# Modulo_de_expansao_01.net
KiCad netlist of a schematic drawn in EAGLE
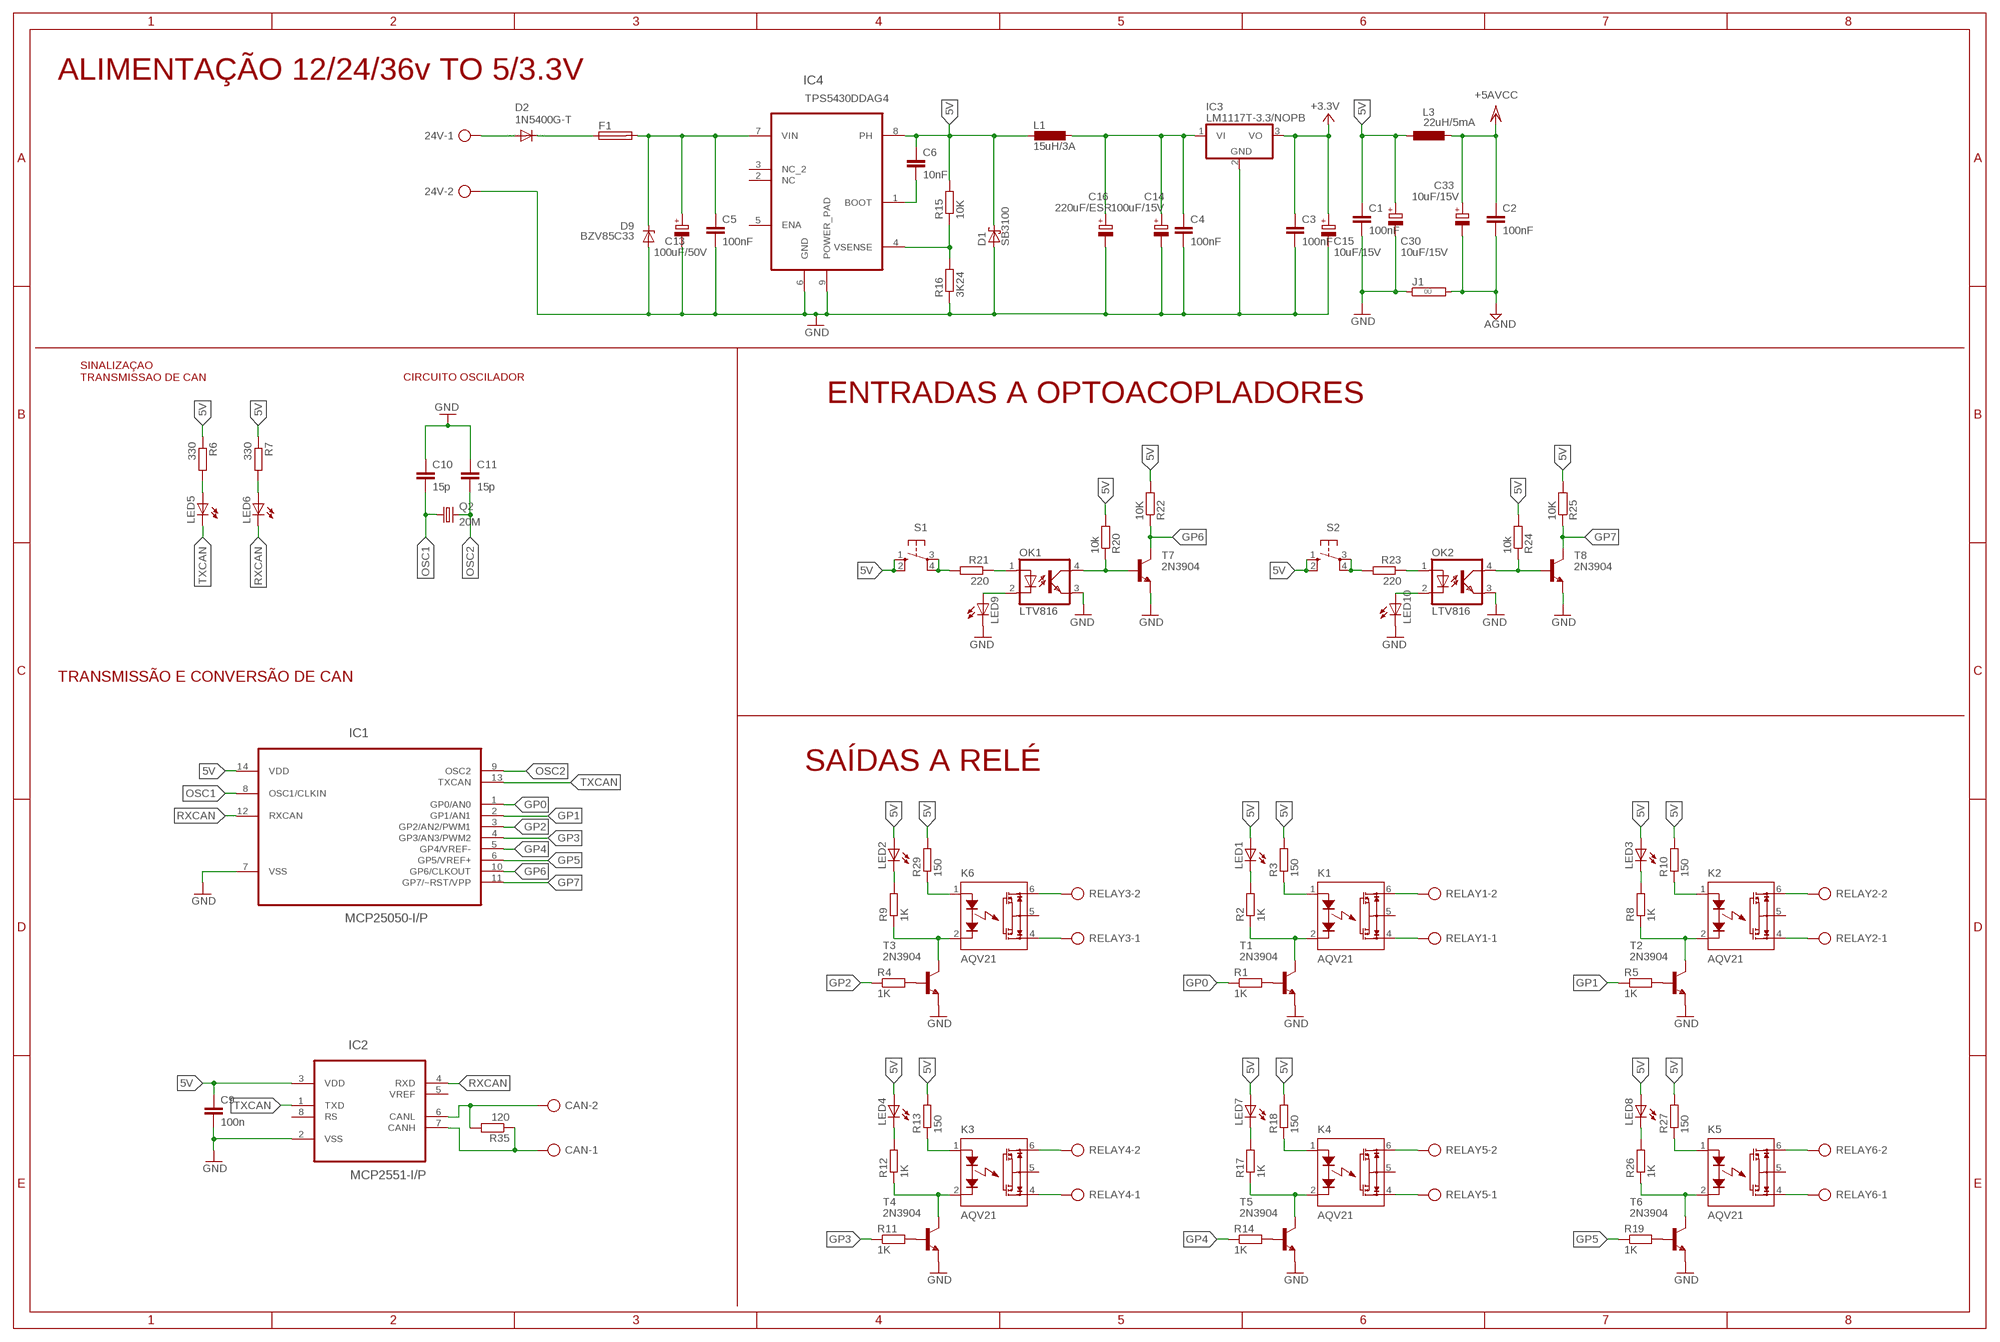
[diagram p0: schematic, sheet 1]

(export (version "E")
  (design (tool "Eeschema 10.0.6"))
  (components
    (comp (ref "24V")
      (value "AK300/2")
      (footprint "eagle-import:AK300_2")
      (libsource (lib "eagle-import") (part "AK300/2"))
    )
    (comp (ref "C1")
      (value "100nF")
      (footprint "eagle-import:C050-024X044")
      (libsource (lib "eagle-import") (part "C-EU050-024X044"))
    )
    (comp (ref "C2")
      (value "100nF")
      (footprint "eagle-import:C050-024X044")
      (libsource (lib "eagle-import") (part "C-EU050-024X044"))
    )
    (comp (ref "C3")
      (value "100nF")
      (footprint "eagle-import:C050-024X044")
      (libsource (lib "eagle-import") (part "C-EU050-024X044"))
    )
    (comp (ref "C4")
      (value "100nF")
      (footprint "eagle-import:C050-024X044")
      (libsource (lib "eagle-import") (part "C-EU050-024X044"))
    )
    (comp (ref "C5")
      (value "100nF")
      (footprint "eagle-import:C050-024X044")
      (libsource (lib "eagle-import") (part "C-EU050-024X044"))
    )
    (comp (ref "C6")
      (value "10nF")
      (footprint "eagle-import:C025-025X050")
      (libsource (lib "eagle-import") (part "C-EU025-025X050"))
    )
    (comp (ref "C9")
      (value "100n")
      (footprint "eagle-import:C050-024X044")
      (libsource (lib "eagle-import") (part "C-EU050-024X044"))
    )
    (comp (ref "C10")
      (value "15p")
      (footprint "eagle-import:C025-024X044")
      (libsource (lib "eagle-import") (part "C-EU025-024X044"))
    )
    (comp (ref "C11")
      (value "15p")
      (footprint "eagle-import:C025-024X044")
      (libsource (lib "eagle-import") (part "C-EU025-024X044"))
    )
    (comp (ref "C13")
      (value "100uF/50V")
      (footprint "eagle-import:E3,5-10")
      (libsource (lib "eagle-import") (part "CPOL-EUE3.5-10"))
    )
    (comp (ref "C14")
      (value "100uF/15V")
      (footprint "eagle-import:E2-5")
      (libsource (lib "eagle-import") (part "CPOL-EUE2-5"))
    )
    (comp (ref "C15")
      (value "10uF/15V")
      (footprint "eagle-import:E2-5")
      (libsource (lib "eagle-import") (part "CPOL-EUE2-5"))
    )
    (comp (ref "C16")
      (value "220uF/ESR")
      (footprint "eagle-import:E2,5-7")
      (libsource (lib "eagle-import") (part "CPOL-EUE2.5-7"))
    )
    (comp (ref "C30")
      (value "10uF/15V")
      (footprint "eagle-import:E2,5-6")
      (libsource (lib "eagle-import") (part "CPOL-EUE2.5-6"))
    )
    (comp (ref "C33")
      (value "10uF/15V")
      (footprint "eagle-import:E2,5-6")
      (libsource (lib "eagle-import") (part "CPOL-EUE2.5-6"))
    )
    (comp (ref "CAN")
      (value "AK300/2")
      (footprint "eagle-import:AK300_2")
      (libsource (lib "eagle-import") (part "AK300/2"))
    )
    (comp (ref "D1")
      (value "SB3100")
      (footprint "eagle-import:DO201T15")
      (libsource (lib "eagle-import") (part "SCHOTTKY-DIODEDO201T15"))
    )
    (comp (ref "D2")
      (value "1N5400G-T")
      (footprint "eagle-import:DO201-15")
      (libsource (lib "eagle-import") (part "1N5624"))
    )
    (comp (ref "D9")
      (value "BZV85C33")
      (footprint "eagle-import:DO34Z7")
      (libsource (lib "eagle-import") (part "BZV10"))
    )
    (comp (ref "F1")
      (value "TR5")
      (footprint "eagle-import:TR5")
      (libsource (lib "eagle-import") (part "TR5"))
    )
    (comp (ref "IC1")
      (value "MCP25050-I/P")
      (footprint "eagle-import:DIP254P762X432-14")
      (libsource (lib "eagle-import") (part "MCP25050-I/P"))
    )
    (comp (ref "IC2")
      (value "MCP2551-I/P")
      (footprint "eagle-import:DIP254P762X432-8")
      (libsource (lib "eagle-import") (part "MCP2551-I/P"))
    )
    (comp (ref "IC3")
      (value "LM1117T-3.3/NOPB")
      (footprint "eagle-import:TO220H")
      (libsource (lib "eagle-import") (part "LM340?-H12"))
    )
    (comp (ref "IC4")
      (value "TPS5430DDAG4")
      (footprint "eagle-import:SOIC127P600X170-9N")
      (fields (field (name "MPN") "TPS5430DDAG4"))
      (libsource (lib "eagle-import") (part "TPS5430DDAG4"))
    )
    (comp (ref "J1")
      (value "0R")
      (footprint "eagle-import:0R_10")
      (libsource (lib "eagle-import") (part "0R"))
    )
    (comp (ref "K1")
      (value "AQV21")
      (footprint "eagle-import:DIL06")
      (fields (field (name "MPN") "AQV210"))
      (libsource (lib "eagle-import") (part "AQV21"))
    )
    (comp (ref "K2")
      (value "AQV21")
      (footprint "eagle-import:DIL06")
      (fields (field (name "MPN") "AQV210"))
      (libsource (lib "eagle-import") (part "AQV21"))
    )
    (comp (ref "K3")
      (value "AQV21")
      (footprint "eagle-import:DIL06")
      (fields (field (name "MPN") "AQV210"))
      (libsource (lib "eagle-import") (part "AQV21"))
    )
    (comp (ref "K4")
      (value "AQV21")
      (footprint "eagle-import:DIL06")
      (fields (field (name "MPN") "AQV210"))
      (libsource (lib "eagle-import") (part "AQV21"))
    )
    (comp (ref "K5")
      (value "AQV21")
      (footprint "eagle-import:DIL06")
      (fields (field (name "MPN") "AQV210"))
      (libsource (lib "eagle-import") (part "AQV21"))
    )
    (comp (ref "K6")
      (value "AQV21")
      (footprint "eagle-import:DIL06")
      (fields (field (name "MPN") "AQV210"))
      (libsource (lib "eagle-import") (part "AQV21"))
    )
    (comp (ref "L1")
      (value "15uH/3A")
      (footprint "eagle-import:6000-XXXX-RC")
      (libsource (lib "eagle-import") (part "L-EU6000-XXX-RC"))
    )
    (comp (ref "L3")
      (value "22uH/5mA")
      (footprint "eagle-import:6000-XXXX-RC")
      (libsource (lib "eagle-import") (part "L-EU6000-XXX-RC"))
    )
    (comp (ref "LED1")
      (value "LED3MM")
      (footprint "eagle-import:LED3MM")
      (libsource (lib "eagle-import") (part "LED3MM"))
    )
    (comp (ref "LED2")
      (value "LED3MM")
      (footprint "eagle-import:LED3MM")
      (libsource (lib "eagle-import") (part "LED3MM"))
    )
    (comp (ref "LED3")
      (value "LED3MM")
      (footprint "eagle-import:LED3MM")
      (libsource (lib "eagle-import") (part "LED3MM"))
    )
    (comp (ref "LED4")
      (value "LED3MM")
      (footprint "eagle-import:LED3MM")
      (libsource (lib "eagle-import") (part "LED3MM"))
    )
    (comp (ref "LED5")
      (value "LED3MM")
      (footprint "eagle-import:LED3MM")
      (libsource (lib "eagle-import") (part "LED3MM"))
    )
    (comp (ref "LED6")
      (value "LED3MM")
      (footprint "eagle-import:LED3MM")
      (libsource (lib "eagle-import") (part "LED3MM"))
    )
    (comp (ref "LED7")
      (value "LED3MM")
      (footprint "eagle-import:LED3MM")
      (libsource (lib "eagle-import") (part "LED3MM"))
    )
    (comp (ref "LED8")
      (value "LED3MM")
      (footprint "eagle-import:LED3MM")
      (libsource (lib "eagle-import") (part "LED3MM"))
    )
    (comp (ref "LED9")
      (value "LED3MM")
      (footprint "eagle-import:LED3MM")
      (libsource (lib "eagle-import") (part "LED3MM"))
    )
    (comp (ref "LED10")
      (value "LED3MM")
      (footprint "eagle-import:LED3MM")
      (libsource (lib "eagle-import") (part "LED3MM"))
    )
    (comp (ref "OK1")
      (value "LTV816")
      (footprint "eagle-import:DIL04")
      (libsource (lib "eagle-import") (part "LTV816"))
    )
    (comp (ref "OK2")
      (value "LTV816")
      (footprint "eagle-import:DIL04")
      (libsource (lib "eagle-import") (part "LTV816"))
    )
    (comp (ref "Q2")
      (value "20M")
      (footprint "eagle-import:HC49_S")
      (libsource (lib "eagle-import") (part "CRYSTALHC49S"))
    )
    (comp (ref "R1")
      (value "1K")
      (footprint "eagle-import:0207_10")
      (libsource (lib "eagle-import") (part "R-EU_0207/10"))
    )
    (comp (ref "R2")
      (value "1K")
      (footprint "eagle-import:0207_10")
      (libsource (lib "eagle-import") (part "R-EU_0207/10"))
    )
    (comp (ref "R3")
      (value "150")
      (footprint "eagle-import:0207_10")
      (libsource (lib "eagle-import") (part "R-EU_0207/10"))
    )
    (comp (ref "R4")
      (value "1K")
      (footprint "eagle-import:0207_10")
      (libsource (lib "eagle-import") (part "R-EU_0207/10"))
    )
    (comp (ref "R5")
      (value "1K")
      (footprint "eagle-import:0207_10")
      (libsource (lib "eagle-import") (part "R-EU_0207/10"))
    )
    (comp (ref "R6")
      (value "330")
      (footprint "eagle-import:0207_10")
      (libsource (lib "eagle-import") (part "R-EU_0207/10"))
    )
    (comp (ref "R7")
      (value "330")
      (footprint "eagle-import:0207_10")
      (libsource (lib "eagle-import") (part "R-EU_0207/10"))
    )
    (comp (ref "R8")
      (value "1K")
      (footprint "eagle-import:0207_10")
      (libsource (lib "eagle-import") (part "R-EU_0207/10"))
    )
    (comp (ref "R9")
      (value "1K")
      (footprint "eagle-import:0207_10")
      (libsource (lib "eagle-import") (part "R-EU_0207/10"))
    )
    (comp (ref "R10")
      (value "150")
      (footprint "eagle-import:0207_10")
      (libsource (lib "eagle-import") (part "R-EU_0207/10"))
    )
    (comp (ref "R11")
      (value "1K")
      (footprint "eagle-import:0207_10")
      (libsource (lib "eagle-import") (part "R-EU_0207/10"))
    )
    (comp (ref "R12")
      (value "1K")
      (footprint "eagle-import:0207_10")
      (libsource (lib "eagle-import") (part "R-EU_0207/10"))
    )
    (comp (ref "R13")
      (value "150")
      (footprint "eagle-import:0207_10")
      (libsource (lib "eagle-import") (part "R-EU_0207/10"))
    )
    (comp (ref "R14")
      (value "1K")
      (footprint "eagle-import:0207_10")
      (libsource (lib "eagle-import") (part "R-EU_0207/10"))
    )
    (comp (ref "R15")
      (value "10K")
      (footprint "eagle-import:0207_10")
      (libsource (lib "eagle-import") (part "R-EU_0207/10"))
    )
    (comp (ref "R16")
      (value "3K24")
      (footprint "eagle-import:0207_10")
      (libsource (lib "eagle-import") (part "R-EU_0207/10"))
    )
    (comp (ref "R17")
      (value "1K")
      (footprint "eagle-import:0207_10")
      (libsource (lib "eagle-import") (part "R-EU_0207/10"))
    )
    (comp (ref "R18")
      (value "150")
      (footprint "eagle-import:0207_10")
      (libsource (lib "eagle-import") (part "R-EU_0207/10"))
    )
    (comp (ref "R19")
      (value "1K")
      (footprint "eagle-import:0207_10")
      (libsource (lib "eagle-import") (part "R-EU_0207/10"))
    )
    (comp (ref "R20")
      (value "10k")
      (footprint "eagle-import:0207_10")
      (libsource (lib "eagle-import") (part "R-EU_0207/10"))
    )
    (comp (ref "R21")
      (value "220")
      (footprint "eagle-import:0207_10")
      (libsource (lib "eagle-import") (part "R-EU_0207/10"))
    )
    (comp (ref "R22")
      (value "10K")
      (footprint "eagle-import:0207_10")
      (libsource (lib "eagle-import") (part "R-EU_0207/10"))
    )
    (comp (ref "R23")
      (value "220")
      (footprint "eagle-import:0207_10")
      (libsource (lib "eagle-import") (part "R-EU_0207/10"))
    )
    (comp (ref "R24")
      (value "10k")
      (footprint "eagle-import:0207_10")
      (libsource (lib "eagle-import") (part "R-EU_0207/10"))
    )
    (comp (ref "R25")
      (value "10K")
      (footprint "eagle-import:0207_10")
      (libsource (lib "eagle-import") (part "R-EU_0207/10"))
    )
    (comp (ref "R26")
      (value "1K")
      (footprint "eagle-import:0207_10")
      (libsource (lib "eagle-import") (part "R-EU_0207/10"))
    )
    (comp (ref "R27")
      (value "150")
      (footprint "eagle-import:0207_10")
      (libsource (lib "eagle-import") (part "R-EU_0207/10"))
    )
    (comp (ref "R29")
      (value "150")
      (footprint "eagle-import:0207_10")
      (libsource (lib "eagle-import") (part "R-EU_0207/10"))
    )
    (comp (ref "R35")
      (value "120")
      (footprint "eagle-import:0207_10")
      (libsource (lib "eagle-import") (part "R-EU_0207/10"))
    )
    (comp (ref "RELAY1")
      (value "AK300/2")
      (footprint "eagle-import:AK300_2")
      (libsource (lib "eagle-import") (part "AK300/2"))
    )
    (comp (ref "RELAY2")
      (value "AK300/2")
      (footprint "eagle-import:AK300_2")
      (libsource (lib "eagle-import") (part "AK300/2"))
    )
    (comp (ref "RELAY3")
      (value "AK300/2")
      (footprint "eagle-import:AK300_2")
      (libsource (lib "eagle-import") (part "AK300/2"))
    )
    (comp (ref "RELAY4")
      (value "AK300/2")
      (footprint "eagle-import:AK300_2")
      (libsource (lib "eagle-import") (part "AK300/2"))
    )
    (comp (ref "RELAY5")
      (value "AK300/2")
      (footprint "eagle-import:AK300_2")
      (libsource (lib "eagle-import") (part "AK300/2"))
    )
    (comp (ref "RELAY6")
      (value "AK300/2")
      (footprint "eagle-import:AK300_2")
      (libsource (lib "eagle-import") (part "AK300/2"))
    )
    (comp (ref "S1")
      (value "10-XX")
      (footprint "eagle-import:B3F-10XX")
      (fields (field (name "MPN") "B3F-1000"))
      (libsource (lib "eagle-import") (part "10-XX"))
    )
    (comp (ref "S2")
      (value "10-XX")
      (footprint "eagle-import:B3F-10XX")
      (fields (field (name "MPN") "B3F-1000"))
      (libsource (lib "eagle-import") (part "10-XX"))
    )
    (comp (ref "T1")
      (value "2N3904")
      (footprint "eagle-import:TO92")
      (libsource (lib "eagle-import") (part "2N3904"))
    )
    (comp (ref "T2")
      (value "2N3904")
      (footprint "eagle-import:TO92")
      (libsource (lib "eagle-import") (part "2N3904"))
    )
    (comp (ref "T3")
      (value "2N3904")
      (footprint "eagle-import:TO92")
      (libsource (lib "eagle-import") (part "2N3904"))
    )
    (comp (ref "T4")
      (value "2N3904")
      (footprint "eagle-import:TO92")
      (libsource (lib "eagle-import") (part "2N3904"))
    )
    (comp (ref "T5")
      (value "2N3904")
      (footprint "eagle-import:TO92")
      (libsource (lib "eagle-import") (part "2N3904"))
    )
    (comp (ref "T6")
      (value "2N3904")
      (footprint "eagle-import:TO92")
      (libsource (lib "eagle-import") (part "2N3904"))
    )
    (comp (ref "T7")
      (value "2N3904")
      (footprint "eagle-import:TO92")
      (libsource (lib "eagle-import") (part "2N3904"))
    )
    (comp (ref "T8")
      (value "2N3904")
      (footprint "eagle-import:TO92")
      (libsource (lib "eagle-import") (part "2N3904"))
    )
  )
  (nets
    (net (code "1") (name "+3.3V") (class "Default")
      (node (ref "C15") (pin "+") (pinfunction "+_+") (pintype "passive"))
      (node (ref "C3") (pin "1") (pinfunction "1_1") (pintype "passive"))
      (node (ref "IC3") (pin "3") (pinfunction "VO_3") (pintype "passive"))
    )
    (net (code "2") (name "+5AVCC") (class "Default")
      (node (ref "C2") (pin "1") (pinfunction "1_1") (pintype "passive"))
      (node (ref "C33") (pin "+") (pinfunction "+_+") (pintype "passive"))
      (node (ref "L3") (pin "2") (pinfunction "2_2") (pintype "passive"))
    )
    (net (code "3") (name "5V") (class "Default")
      (node (ref "C1") (pin "1") (pinfunction "1_1") (pintype "passive"))
      (node (ref "C30") (pin "+") (pinfunction "+_+") (pintype "passive"))
      (node (ref "C6") (pin "1") (pinfunction "1_1") (pintype "passive"))
      (node (ref "C9") (pin "1") (pinfunction "1_1") (pintype "passive"))
      (node (ref "D1") (pin "C") (pinfunction "C_C") (pintype "passive"))
      (node (ref "IC1") (pin "14") (pinfunction "VDD_14") (pintype "power_in"))
      (node (ref "IC2") (pin "3") (pinfunction "VDD_3") (pintype "power_in"))
      (node (ref "IC4") (pin "8") (pinfunction "PH_8") (pintype "input"))
      (node (ref "L1") (pin "2") (pinfunction "2_2") (pintype "passive"))
      (node (ref "L3") (pin "1") (pinfunction "1_1") (pintype "passive"))
      (node (ref "LED1") (pin "A") (pinfunction "A_A") (pintype "passive"))
      (node (ref "LED2") (pin "A") (pinfunction "A_A") (pintype "passive"))
      (node (ref "LED3") (pin "A") (pinfunction "A_A") (pintype "passive"))
      (node (ref "LED4") (pin "A") (pinfunction "A_A") (pintype "passive"))
      (node (ref "LED7") (pin "A") (pinfunction "A_A") (pintype "passive"))
      (node (ref "LED8") (pin "A") (pinfunction "A_A") (pintype "passive"))
      (node (ref "R10") (pin "2") (pinfunction "2_2") (pintype "passive"))
      (node (ref "R13") (pin "2") (pinfunction "2_2") (pintype "passive"))
      (node (ref "R15") (pin "2") (pinfunction "2_2") (pintype "passive"))
      (node (ref "R18") (pin "2") (pinfunction "2_2") (pintype "passive"))
      (node (ref "R20") (pin "2") (pinfunction "2_2") (pintype "passive"))
      (node (ref "R22") (pin "2") (pinfunction "2_2") (pintype "passive"))
      (node (ref "R24") (pin "2") (pinfunction "2_2") (pintype "passive"))
      (node (ref "R25") (pin "2") (pinfunction "2_2") (pintype "passive"))
      (node (ref "R27") (pin "2") (pinfunction "2_2") (pintype "passive"))
      (node (ref "R29") (pin "2") (pinfunction "2_2") (pintype "passive"))
      (node (ref "R3") (pin "2") (pinfunction "2_2") (pintype "passive"))
      (node (ref "R6") (pin "1") (pinfunction "1_1") (pintype "passive"))
      (node (ref "R7") (pin "1") (pinfunction "1_1") (pintype "passive"))
      (node (ref "S1") (pin "1") (pinfunction "S_1") (pintype "passive"))
      (node (ref "S1") (pin "2") (pinfunction "S1_2") (pintype "passive"))
      (node (ref "S2") (pin "1") (pinfunction "S_1") (pintype "passive"))
      (node (ref "S2") (pin "2") (pinfunction "S1_2") (pintype "passive"))
    )
    (net (code "4") (name "AGND") (class "Default")
      (node (ref "C2") (pin "2") (pinfunction "2_2") (pintype "passive"))
      (node (ref "C33") (pin "-") (pinfunction "-_-") (pintype "passive"))
      (node (ref "J1") (pin "2") (pinfunction "2_2") (pintype "passive"))
    )
    (net (code "5") (name "GND") (class "Default")
      (node (ref "24V") (pin "2") (pinfunction "KL_2") (pintype "passive"))
      (node (ref "C1") (pin "2") (pinfunction "2_2") (pintype "passive"))
      (node (ref "C10") (pin "1") (pinfunction "1_1") (pintype "passive"))
      (node (ref "C11") (pin "1") (pinfunction "1_1") (pintype "passive"))
      (node (ref "C13") (pin "-") (pinfunction "-_-") (pintype "passive"))
      (node (ref "C14") (pin "-") (pinfunction "-_-") (pintype "passive"))
      (node (ref "C15") (pin "-") (pinfunction "-_-") (pintype "passive"))
      (node (ref "C16") (pin "-") (pinfunction "-_-") (pintype "passive"))
      (node (ref "C3") (pin "2") (pinfunction "2_2") (pintype "passive"))
      (node (ref "C30") (pin "-") (pinfunction "-_-") (pintype "passive"))
      (node (ref "C4") (pin "2") (pinfunction "2_2") (pintype "passive"))
      (node (ref "C5") (pin "2") (pinfunction "2_2") (pintype "passive"))
      (node (ref "C9") (pin "2") (pinfunction "2_2") (pintype "passive"))
      (node (ref "D1") (pin "A") (pinfunction "A_A") (pintype "passive"))
      (node (ref "D9") (pin "A") (pinfunction "A_A") (pintype "passive"))
      (node (ref "IC1") (pin "7") (pinfunction "VSS_7") (pintype "passive"))
      (node (ref "IC2") (pin "2") (pinfunction "VSS_2") (pintype "power_in"))
      (node (ref "IC3") (pin "2") (pinfunction "GND_2") (pintype "passive"))
      (node (ref "IC4") (pin "6") (pinfunction "GND_6") (pintype "passive"))
      (node (ref "IC4") (pin "9") (pinfunction "POWER_PAD_9") (pintype "passive"))
      (node (ref "J1") (pin "1") (pinfunction "1_1") (pintype "passive"))
      (node (ref "LED10") (pin "K") (pinfunction "C_K") (pintype "passive"))
      (node (ref "LED9") (pin "K") (pinfunction "C_K") (pintype "passive"))
      (node (ref "OK1") (pin "3") (pinfunction "EMIT_3") (pintype "passive"))
      (node (ref "OK2") (pin "3") (pinfunction "EMIT_3") (pintype "passive"))
      (node (ref "R16") (pin "1") (pinfunction "1_1") (pintype "passive"))
      (node (ref "T1") (pin "3") (pinfunction "E_3") (pintype "passive"))
      (node (ref "T2") (pin "3") (pinfunction "E_3") (pintype "passive"))
      (node (ref "T3") (pin "3") (pinfunction "E_3") (pintype "passive"))
      (node (ref "T4") (pin "3") (pinfunction "E_3") (pintype "passive"))
      (node (ref "T5") (pin "3") (pinfunction "E_3") (pintype "passive"))
      (node (ref "T6") (pin "3") (pinfunction "E_3") (pintype "passive"))
      (node (ref "T7") (pin "3") (pinfunction "E_3") (pintype "passive"))
      (node (ref "T8") (pin "3") (pinfunction "E_3") (pintype "passive"))
    )
    (net (code "6") (name "GP0") (class "Default")
      (node (ref "IC1") (pin "1") (pinfunction "GP0/AN0_1") (pintype "bidirectional"))
      (node (ref "R1") (pin "1") (pinfunction "1_1") (pintype "passive"))
    )
    (net (code "7") (name "GP1") (class "Default")
      (node (ref "IC1") (pin "2") (pinfunction "GP1/AN1_2") (pintype "bidirectional"))
      (node (ref "R5") (pin "1") (pinfunction "1_1") (pintype "passive"))
    )
    (net (code "8") (name "GP2") (class "Default")
      (node (ref "IC1") (pin "3") (pinfunction "GP2/AN2/PWM1_3") (pintype "bidirectional"))
      (node (ref "R4") (pin "1") (pinfunction "1_1") (pintype "passive"))
    )
    (net (code "9") (name "GP3") (class "Default")
      (node (ref "IC1") (pin "4") (pinfunction "GP3/AN3/PWM2_4") (pintype "bidirectional"))
      (node (ref "R11") (pin "1") (pinfunction "1_1") (pintype "passive"))
    )
    (net (code "10") (name "GP4") (class "Default")
      (node (ref "IC1") (pin "5") (pinfunction "GP4/VREF-_5") (pintype "bidirectional"))
      (node (ref "R14") (pin "1") (pinfunction "1_1") (pintype "passive"))
    )
    (net (code "11") (name "GP5") (class "Default")
      (node (ref "IC1") (pin "6") (pinfunction "GP5/VREF+_6") (pintype "bidirectional"))
      (node (ref "R19") (pin "1") (pinfunction "1_1") (pintype "passive"))
    )
    (net (code "12") (name "GP6") (class "Default")
      (node (ref "IC1") (pin "10") (pinfunction "GP6/CLKOUT_10") (pintype "bidirectional"))
      (node (ref "R22") (pin "1") (pinfunction "1_1") (pintype "passive"))
      (node (ref "T7") (pin "1") (pinfunction "C_1") (pintype "passive"))
    )
    (net (code "13") (name "GP7") (class "Default")
      (node (ref "IC1") (pin "11") (pinfunction "GP7/~{RST/VPP}_11") (pintype "bidirectional"))
      (node (ref "R25") (pin "1") (pinfunction "1_1") (pintype "passive"))
      (node (ref "T8") (pin "1") (pinfunction "C_1") (pintype "passive"))
    )
    (net (code "14") (name "Net-(24VA-KL)") (class "Default")
      (node (ref "24V") (pin "1") (pinfunction "KL_1") (pintype "passive"))
      (node (ref "D2") (pin "A") (pinfunction "A_A") (pintype "passive"))
    )
    (net (code "15") (name "Net-(CANA-KL)") (class "Default")
      (node (ref "CAN") (pin "1") (pinfunction "KL_1") (pintype "passive"))
      (node (ref "IC2") (pin "7") (pinfunction "CANH_7") (pintype "bidirectional"))
      (node (ref "R35") (pin "1") (pinfunction "1_1") (pintype "passive"))
    )
    (net (code "16") (name "Net-(CANB-KL)") (class "Default")
      (node (ref "CAN") (pin "2") (pinfunction "KL_2") (pintype "passive"))
      (node (ref "IC2") (pin "6") (pinfunction "CANL_6") (pintype "bidirectional"))
      (node (ref "R35") (pin "2") (pinfunction "2_2") (pintype "passive"))
    )
    (net (code "17") (name "Net-(D2-PadC)") (class "Default")
      (node (ref "D2") (pin "C") (pinfunction "C_C") (pintype "passive"))
      (node (ref "F1") (pin "1") (pinfunction "1_1") (pintype "passive"))
    )
    (net (code "18") (name "Net-(IC3-VI)") (class "Default")
      (node (ref "C14") (pin "+") (pinfunction "+_+") (pintype "passive"))
      (node (ref "C16") (pin "+") (pinfunction "+_+") (pintype "passive"))
      (node (ref "C4") (pin "1") (pinfunction "1_1") (pintype "passive"))
      (node (ref "IC3") (pin "1") (pinfunction "VI_1") (pintype "input"))
      (node (ref "L1") (pin "1") (pinfunction "1_1") (pintype "passive"))
    )
    (net (code "19") (name "Net-(IC4-BOOT)") (class "Default")
      (node (ref "C6") (pin "2") (pinfunction "2_2") (pintype "passive"))
      (node (ref "IC4") (pin "1") (pinfunction "BOOT_1") (pintype "passive"))
    )
    (net (code "20") (name "Net-(IC4-VIN)") (class "Default")
      (node (ref "C13") (pin "+") (pinfunction "+_+") (pintype "passive"))
      (node (ref "C5") (pin "1") (pinfunction "1_1") (pintype "passive"))
      (node (ref "D9") (pin "C") (pinfunction "C_C") (pintype "passive"))
      (node (ref "F1") (pin "2") (pinfunction "2_2") (pintype "passive"))
      (node (ref "IC4") (pin "7") (pinfunction "VIN_7") (pintype "power_in"))
    )
    (net (code "21") (name "Net-(IC4-VSENSE)") (class "Default")
      (node (ref "IC4") (pin "4") (pinfunction "VSENSE_4") (pintype "output"))
      (node (ref "R15") (pin "1") (pinfunction "1_1") (pintype "passive"))
      (node (ref "R16") (pin "2") (pinfunction "2_2") (pintype "passive"))
    )
    (net (code "22") (name "Net-(K1-A)") (class "Default")
      (node (ref "K1") (pin "1") (pinfunction "A_1") (pintype "passive"))
      (node (ref "R3") (pin "1") (pinfunction "1_1") (pintype "passive"))
    )
    (net (code "23") (name "Net-(K1-D1)") (class "Default")
      (node (ref "K1") (pin "6") (pinfunction "D1_6") (pintype "passive"))
      (node (ref "RELAY1") (pin "2") (pinfunction "KL_2") (pintype "passive"))
    )
    (net (code "24") (name "Net-(K1-D2)") (class "Default")
      (node (ref "K1") (pin "4") (pinfunction "D2_4") (pintype "passive"))
      (node (ref "RELAY1") (pin "1") (pinfunction "KL_1") (pintype "passive"))
    )
    (net (code "25") (name "Net-(K1-K)") (class "Default")
      (node (ref "K1") (pin "2") (pinfunction "K_2") (pintype "passive"))
      (node (ref "R2") (pin "1") (pinfunction "1_1") (pintype "passive"))
      (node (ref "T1") (pin "1") (pinfunction "C_1") (pintype "passive"))
    )
    (net (code "26") (name "Net-(K2-A)") (class "Default")
      (node (ref "K2") (pin "1") (pinfunction "A_1") (pintype "passive"))
      (node (ref "R10") (pin "1") (pinfunction "1_1") (pintype "passive"))
    )
    (net (code "27") (name "Net-(K2-D1)") (class "Default")
      (node (ref "K2") (pin "6") (pinfunction "D1_6") (pintype "passive"))
      (node (ref "RELAY2") (pin "2") (pinfunction "KL_2") (pintype "passive"))
    )
    (net (code "28") (name "Net-(K2-D2)") (class "Default")
      (node (ref "K2") (pin "4") (pinfunction "D2_4") (pintype "passive"))
      (node (ref "RELAY2") (pin "1") (pinfunction "KL_1") (pintype "passive"))
    )
    (net (code "29") (name "Net-(K2-K)") (class "Default")
      (node (ref "K2") (pin "2") (pinfunction "K_2") (pintype "passive"))
      (node (ref "R8") (pin "1") (pinfunction "1_1") (pintype "passive"))
      (node (ref "T2") (pin "1") (pinfunction "C_1") (pintype "passive"))
    )
    (net (code "30") (name "Net-(K3-A)") (class "Default")
      (node (ref "K3") (pin "1") (pinfunction "A_1") (pintype "passive"))
      (node (ref "R13") (pin "1") (pinfunction "1_1") (pintype "passive"))
    )
    (net (code "31") (name "Net-(K3-D1)") (class "Default")
      (node (ref "K3") (pin "6") (pinfunction "D1_6") (pintype "passive"))
      (node (ref "RELAY4") (pin "2") (pinfunction "KL_2") (pintype "passive"))
    )
    (net (code "32") (name "Net-(K3-D2)") (class "Default")
      (node (ref "K3") (pin "4") (pinfunction "D2_4") (pintype "passive"))
      (node (ref "RELAY4") (pin "1") (pinfunction "KL_1") (pintype "passive"))
    )
    (net (code "33") (name "Net-(K3-K)") (class "Default")
      (node (ref "K3") (pin "2") (pinfunction "K_2") (pintype "passive"))
      (node (ref "R12") (pin "1") (pinfunction "1_1") (pintype "passive"))
      (node (ref "T4") (pin "1") (pinfunction "C_1") (pintype "passive"))
    )
    (net (code "34") (name "Net-(K4-A)") (class "Default")
      (node (ref "K4") (pin "1") (pinfunction "A_1") (pintype "passive"))
      (node (ref "R18") (pin "1") (pinfunction "1_1") (pintype "passive"))
    )
    (net (code "35") (name "Net-(K4-D1)") (class "Default")
      (node (ref "K4") (pin "6") (pinfunction "D1_6") (pintype "passive"))
      (node (ref "RELAY5") (pin "2") (pinfunction "KL_2") (pintype "passive"))
    )
    (net (code "36") (name "Net-(K4-D2)") (class "Default")
      (node (ref "K4") (pin "4") (pinfunction "D2_4") (pintype "passive"))
      (node (ref "RELAY5") (pin "1") (pinfunction "KL_1") (pintype "passive"))
    )
    (net (code "37") (name "Net-(K4-K)") (class "Default")
      (node (ref "K4") (pin "2") (pinfunction "K_2") (pintype "passive"))
      (node (ref "R17") (pin "1") (pinfunction "1_1") (pintype "passive"))
      (node (ref "T5") (pin "1") (pinfunction "C_1") (pintype "passive"))
    )
    (net (code "38") (name "Net-(K5-A)") (class "Default")
      (node (ref "K5") (pin "1") (pinfunction "A_1") (pintype "passive"))
      (node (ref "R27") (pin "1") (pinfunction "1_1") (pintype "passive"))
    )
    (net (code "39") (name "Net-(K5-D1)") (class "Default")
      (node (ref "K5") (pin "6") (pinfunction "D1_6") (pintype "passive"))
      (node (ref "RELAY6") (pin "2") (pinfunction "KL_2") (pintype "passive"))
    )
    (net (code "40") (name "Net-(K5-D2)") (class "Default")
      (node (ref "K5") (pin "4") (pinfunction "D2_4") (pintype "passive"))
      (node (ref "RELAY6") (pin "1") (pinfunction "KL_1") (pintype "passive"))
    )
    (net (code "41") (name "Net-(K5-K)") (class "Default")
      (node (ref "K5") (pin "2") (pinfunction "K_2") (pintype "passive"))
      (node (ref "R26") (pin "1") (pinfunction "1_1") (pintype "passive"))
      (node (ref "T6") (pin "1") (pinfunction "C_1") (pintype "passive"))
    )
    (net (code "42") (name "Net-(K6-A)") (class "Default")
      (node (ref "K6") (pin "1") (pinfunction "A_1") (pintype "passive"))
      (node (ref "R29") (pin "1") (pinfunction "1_1") (pintype "passive"))
    )
    (net (code "43") (name "Net-(K6-D1)") (class "Default")
      (node (ref "K6") (pin "6") (pinfunction "D1_6") (pintype "passive"))
      (node (ref "RELAY3") (pin "2") (pinfunction "KL_2") (pintype "passive"))
    )
    (net (code "44") (name "Net-(K6-D2)") (class "Default")
      (node (ref "K6") (pin "4") (pinfunction "D2_4") (pintype "passive"))
      (node (ref "RELAY3") (pin "1") (pinfunction "KL_1") (pintype "passive"))
    )
    (net (code "45") (name "Net-(K6-K)") (class "Default")
      (node (ref "K6") (pin "2") (pinfunction "K_2") (pintype "passive"))
      (node (ref "R9") (pin "1") (pinfunction "1_1") (pintype "passive"))
      (node (ref "T3") (pin "1") (pinfunction "C_1") (pintype "passive"))
    )
    (net (code "46") (name "Net-(LED1-C)") (class "Default")
      (node (ref "LED1") (pin "K") (pinfunction "C_K") (pintype "passive"))
      (node (ref "R2") (pin "2") (pinfunction "2_2") (pintype "passive"))
    )
    (net (code "47") (name "Net-(LED2-C)") (class "Default")
      (node (ref "LED2") (pin "K") (pinfunction "C_K") (pintype "passive"))
      (node (ref "R9") (pin "2") (pinfunction "2_2") (pintype "passive"))
    )
    (net (code "48") (name "Net-(LED3-C)") (class "Default")
      (node (ref "LED3") (pin "K") (pinfunction "C_K") (pintype "passive"))
      (node (ref "R8") (pin "2") (pinfunction "2_2") (pintype "passive"))
    )
    (net (code "49") (name "Net-(LED4-C)") (class "Default")
      (node (ref "LED4") (pin "K") (pinfunction "C_K") (pintype "passive"))
      (node (ref "R12") (pin "2") (pinfunction "2_2") (pintype "passive"))
    )
    (net (code "50") (name "Net-(LED5-PadA)") (class "Default")
      (node (ref "LED5") (pin "A") (pinfunction "A_A") (pintype "passive"))
      (node (ref "R6") (pin "2") (pinfunction "2_2") (pintype "passive"))
    )
    (net (code "51") (name "Net-(LED6-PadA)") (class "Default")
      (node (ref "LED6") (pin "A") (pinfunction "A_A") (pintype "passive"))
      (node (ref "R7") (pin "2") (pinfunction "2_2") (pintype "passive"))
    )
    (net (code "52") (name "Net-(LED7-C)") (class "Default")
      (node (ref "LED7") (pin "K") (pinfunction "C_K") (pintype "passive"))
      (node (ref "R17") (pin "2") (pinfunction "2_2") (pintype "passive"))
    )
    (net (code "53") (name "Net-(LED8-C)") (class "Default")
      (node (ref "LED8") (pin "K") (pinfunction "C_K") (pintype "passive"))
      (node (ref "R26") (pin "2") (pinfunction "2_2") (pintype "passive"))
    )
    (net (code "54") (name "Net-(OK1-A)") (class "Default")
      (node (ref "OK1") (pin "1") (pinfunction "A_1") (pintype "passive"))
      (node (ref "R21") (pin "1") (pinfunction "1_1") (pintype "passive"))
    )
    (net (code "55") (name "Net-(OK1-C)") (class "Default")
      (node (ref "LED9") (pin "A") (pinfunction "A_A") (pintype "passive"))
      (node (ref "OK1") (pin "2") (pinfunction "C_2") (pintype "passive"))
    )
    (net (code "56") (name "Net-(OK1-COL)") (class "Default")
      (node (ref "OK1") (pin "4") (pinfunction "COL_4") (pintype "passive"))
      (node (ref "R20") (pin "1") (pinfunction "1_1") (pintype "passive"))
      (node (ref "T7") (pin "2") (pinfunction "B_2") (pintype "passive"))
    )
    (net (code "57") (name "Net-(OK2-A)") (class "Default")
      (node (ref "OK2") (pin "1") (pinfunction "A_1") (pintype "passive"))
      (node (ref "R23") (pin "1") (pinfunction "1_1") (pintype "passive"))
    )
    (net (code "58") (name "Net-(OK2-C)") (class "Default")
      (node (ref "LED10") (pin "A") (pinfunction "A_A") (pintype "passive"))
      (node (ref "OK2") (pin "2") (pinfunction "C_2") (pintype "passive"))
    )
    (net (code "59") (name "Net-(OK2-COL)") (class "Default")
      (node (ref "OK2") (pin "4") (pinfunction "COL_4") (pintype "passive"))
      (node (ref "R24") (pin "1") (pinfunction "1_1") (pintype "passive"))
      (node (ref "T8") (pin "2") (pinfunction "B_2") (pintype "passive"))
    )
    (net (code "60") (name "Net-(S1-P)") (class "Default")
      (node (ref "R21") (pin "2") (pinfunction "2_2") (pintype "passive"))
      (node (ref "S1") (pin "3") (pinfunction "P_3") (pintype "passive"))
      (node (ref "S1") (pin "4") (pinfunction "P1_4") (pintype "passive"))
    )
    (net (code "61") (name "Net-(S2-P)") (class "Default")
      (node (ref "R23") (pin "2") (pinfunction "2_2") (pintype "passive"))
      (node (ref "S2") (pin "3") (pinfunction "P_3") (pintype "passive"))
      (node (ref "S2") (pin "4") (pinfunction "P1_4") (pintype "passive"))
    )
    (net (code "62") (name "Net-(T1-B)") (class "Default")
      (node (ref "R1") (pin "2") (pinfunction "2_2") (pintype "passive"))
      (node (ref "T1") (pin "2") (pinfunction "B_2") (pintype "passive"))
    )
    (net (code "63") (name "Net-(T2-B)") (class "Default")
      (node (ref "R5") (pin "2") (pinfunction "2_2") (pintype "passive"))
      (node (ref "T2") (pin "2") (pinfunction "B_2") (pintype "passive"))
    )
    (net (code "64") (name "Net-(T3-B)") (class "Default")
      (node (ref "R4") (pin "2") (pinfunction "2_2") (pintype "passive"))
      (node (ref "T3") (pin "2") (pinfunction "B_2") (pintype "passive"))
    )
    (net (code "65") (name "Net-(T4-B)") (class "Default")
      (node (ref "R11") (pin "2") (pinfunction "2_2") (pintype "passive"))
      (node (ref "T4") (pin "2") (pinfunction "B_2") (pintype "passive"))
    )
    (net (code "66") (name "Net-(T5-B)") (class "Default")
      (node (ref "R14") (pin "2") (pinfunction "2_2") (pintype "passive"))
      (node (ref "T5") (pin "2") (pinfunction "B_2") (pintype "passive"))
    )
    (net (code "67") (name "Net-(T6-B)") (class "Default")
      (node (ref "R19") (pin "2") (pinfunction "2_2") (pintype "passive"))
      (node (ref "T6") (pin "2") (pinfunction "B_2") (pintype "passive"))
    )
    (net (code "68") (name "OSC1") (class "Default")
      (node (ref "C10") (pin "2") (pinfunction "2_2") (pintype "passive"))
      (node (ref "IC1") (pin "8") (pinfunction "OSC1/CLKIN_8") (pintype "input"))
      (node (ref "Q2") (pin "1") (pinfunction "1_1") (pintype "passive"))
    )
    (net (code "69") (name "OSC2") (class "Default")
      (node (ref "C11") (pin "2") (pinfunction "2_2") (pintype "passive"))
      (node (ref "IC1") (pin "9") (pinfunction "OSC2_9") (pintype "output"))
      (node (ref "Q2") (pin "2") (pinfunction "2_2") (pintype "passive"))
    )
    (net (code "70") (name "RXCAN") (class "Default")
      (node (ref "IC1") (pin "12") (pinfunction "RXCAN_12") (pintype "input"))
      (node (ref "IC2") (pin "4") (pinfunction "RXD_4") (pintype "output"))
      (node (ref "LED6") (pin "K") (pinfunction "C_K") (pintype "passive"))
    )
    (net (code "71") (name "TXCAN") (class "Default")
      (node (ref "IC1") (pin "13") (pinfunction "TXCAN_13") (pintype "output"))
      (node (ref "IC2") (pin "1") (pinfunction "TXD_1") (pintype "input"))
      (node (ref "LED5") (pin "K") (pinfunction "C_K") (pintype "passive"))
    )
    (net (code "72") (name "unconnected-(IC2-RS-Pad8)") (class "Default")
      (node (ref "IC2") (pin "8") (pinfunction "RS_8") (pintype "input"))
    )
    (net (code "73") (name "unconnected-(IC2-VREF-Pad5)") (class "Default")
      (node (ref "IC2") (pin "5") (pinfunction "VREF_5") (pintype "output"))
    )
    (net (code "74") (name "unconnected-(IC4-ENA-Pad5)") (class "Default")
      (node (ref "IC4") (pin "5") (pinfunction "ENA_5") (pintype "input"))
    )
    (net (code "75") (name "unconnected-(IC4-NC-Pad2)") (class "Default")
      (node (ref "IC4") (pin "2") (pinfunction "NC_2") (pintype "no_connect"))
    )
    (net (code "76") (name "unconnected-(IC4-NC_2-Pad3)") (class "Default")
      (node (ref "IC4") (pin "3") (pinfunction "NC_2_3") (pintype "no_connect"))
    )
    (net (code "77") (name "unconnected-(K1-S-Pad5)") (class "Default")
      (node (ref "K1") (pin "5") (pinfunction "S_5") (pintype "passive"))
    )
    (net (code "78") (name "unconnected-(K2-S-Pad5)") (class "Default")
      (node (ref "K2") (pin "5") (pinfunction "S_5") (pintype "passive"))
    )
    (net (code "79") (name "unconnected-(K3-S-Pad5)") (class "Default")
      (node (ref "K3") (pin "5") (pinfunction "S_5") (pintype "passive"))
    )
    (net (code "80") (name "unconnected-(K4-S-Pad5)") (class "Default")
      (node (ref "K4") (pin "5") (pinfunction "S_5") (pintype "passive"))
    )
    (net (code "81") (name "unconnected-(K5-S-Pad5)") (class "Default")
      (node (ref "K5") (pin "5") (pinfunction "S_5") (pintype "passive"))
    )
    (net (code "82") (name "unconnected-(K6-S-Pad5)") (class "Default")
      (node (ref "K6") (pin "5") (pinfunction "S_5") (pintype "passive"))
    )
  )
)
